# MotorCell.net
KiCad netlist of a schematic drawn in Altium Designer
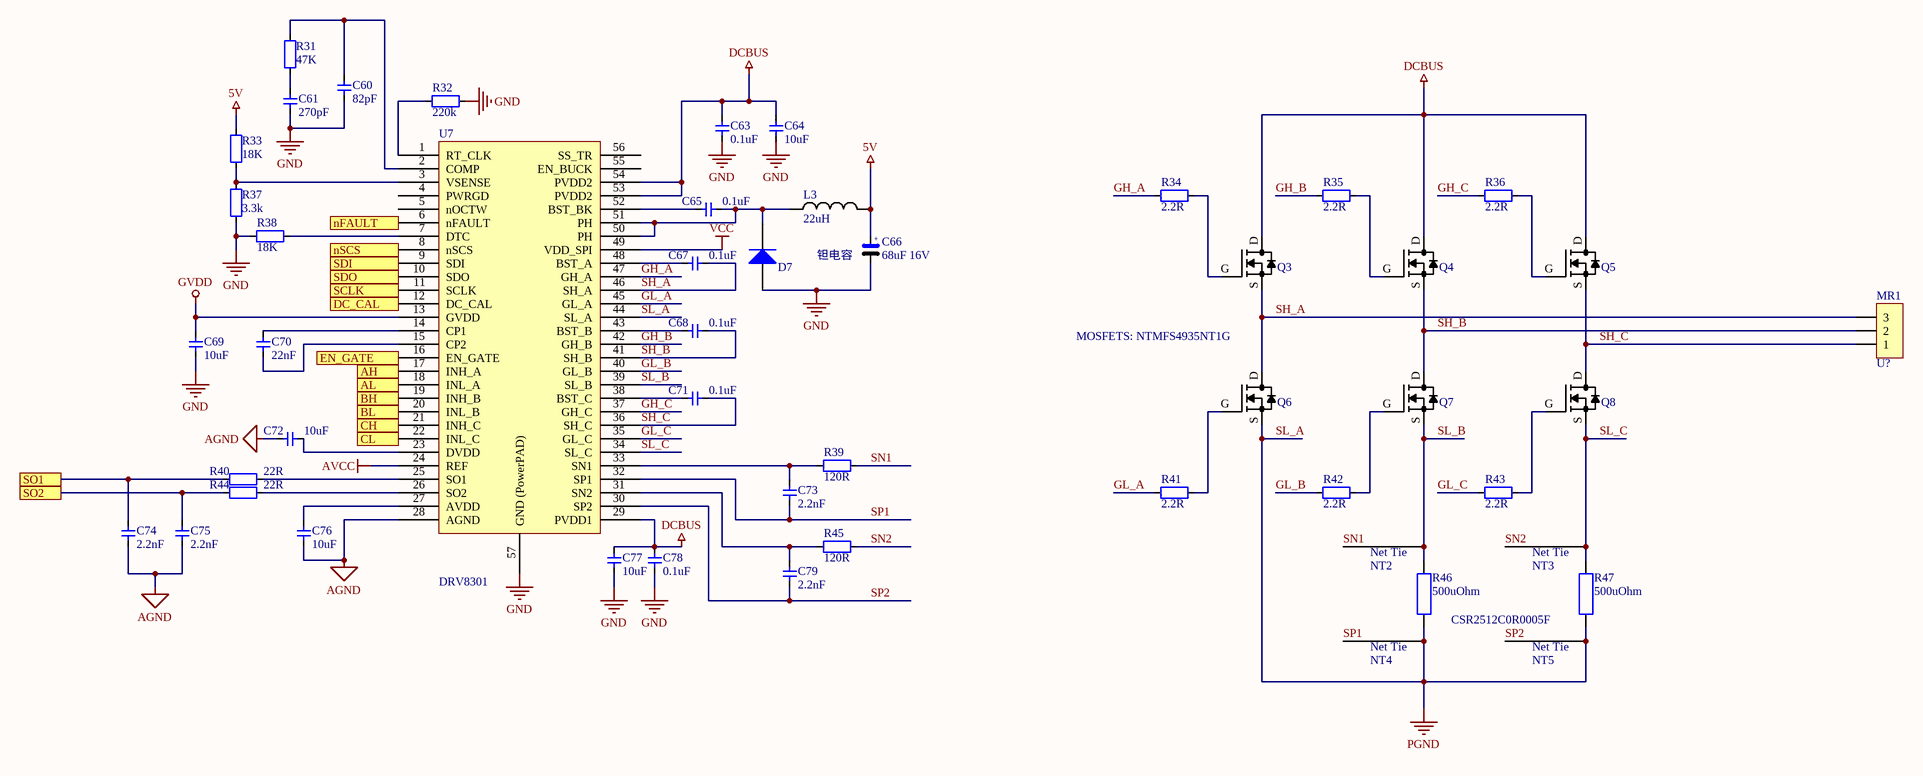
[diagram p0: MotorCell.SchDoc]

(export (version "E")
  (design (tool "Eeschema 10.0.6"))
  (components
    (comp (ref "C60")
      (value "82pF")
      (footprint "CAP_0402")
      (description "Capacitor")
      (libsource (lib "Ctrl_FOC") (part "电容-0402"))
    )
    (comp (ref "C61")
      (value "270pF")
      (footprint "CAP_0402")
      (description "Capacitor")
      (libsource (lib "Ctrl_FOC") (part "电容-0402"))
    )
    (comp (ref "C63")
      (value "0.1uF")
      (footprint "CAP_0603")
      (description "Capacitor")
      (libsource (lib "Ctrl_FOC") (part "电容-0603"))
    )
    (comp (ref "C64")
      (value "10uF")
      (footprint "CAP_0603")
      (description "Capacitor")
      (libsource (lib "Ctrl_FOC") (part "电容-0603"))
    )
    (comp (ref "C65")
      (value "0.1uF")
      (footprint "CAP_0402")
      (description "Capacitor")
      (libsource (lib "Ctrl_FOC") (part "电容-0402"))
    )
    (comp (ref "C66")
      (value "68uF 16V")
      (footprint "CAPCP6032X28N")
      (libsource (lib "Ctrl_FOC") (part "钽电容"))
    )
    (comp (ref "C67")
      (value "0.1uF")
      (footprint "CAP_0603")
      (description "Capacitor")
      (libsource (lib "Ctrl_FOC") (part "电容-0603"))
    )
    (comp (ref "C68")
      (value "0.1uF")
      (footprint "CAP_0603")
      (description "Capacitor")
      (libsource (lib "Ctrl_FOC") (part "电容-0603"))
    )
    (comp (ref "C69")
      (value "10uF")
      (footprint "CAP_0402")
      (description "Capacitor")
      (libsource (lib "Ctrl_FOC") (part "电容-0402"))
    )
    (comp (ref "C70")
      (value "22nF")
      (footprint "CAP_0402")
      (description "Capacitor")
      (libsource (lib "Ctrl_FOC") (part "电容-0402"))
    )
    (comp (ref "C71")
      (value "0.1uF")
      (footprint "CAP_0603")
      (description "Capacitor")
      (libsource (lib "Ctrl_FOC") (part "电容-0603"))
    )
    (comp (ref "C72")
      (value "10uF")
      (footprint "CAP_0402")
      (description "Capacitor")
      (libsource (lib "Ctrl_FOC") (part "电容-0402"))
    )
    (comp (ref "C73")
      (value "2.2nF")
      (footprint "CAP_0402")
      (description "Capacitor")
      (libsource (lib "Ctrl_FOC") (part "电容-0402"))
    )
    (comp (ref "C74")
      (value "2.2nF")
      (footprint "CAP_0402")
      (description "Capacitor")
      (libsource (lib "Ctrl_FOC") (part "电容-0402"))
    )
    (comp (ref "C75")
      (value "2.2nF")
      (footprint "CAP_0402")
      (description "Capacitor")
      (libsource (lib "Ctrl_FOC") (part "电容-0402"))
    )
    (comp (ref "C76")
      (value "10uF")
      (footprint "CAP_0402")
      (description "Capacitor")
      (libsource (lib "Ctrl_FOC") (part "电容-0402"))
    )
    (comp (ref "C77")
      (value "10uF")
      (footprint "CAP_0603")
      (description "Capacitor")
      (libsource (lib "Ctrl_FOC") (part "电容-0603"))
    )
    (comp (ref "C78")
      (value "0.1uF")
      (footprint "CAP_0603")
      (description "Capacitor")
      (libsource (lib "Ctrl_FOC") (part "电容-0603"))
    )
    (comp (ref "C79")
      (value "2.2nF")
      (footprint "CAP_0402")
      (description "Capacitor")
      (libsource (lib "Ctrl_FOC") (part "电容-0402"))
    )
    (comp (ref "D7")
      (value "MBR140SFT1G")
      (footprint "DIOM2717X10N")
      (description "Rectifier Diode, Single, 40 V, 1 A, SOD-123FL, 2, 550 mV")
      (libsource (lib "Ctrl_FOC") (part "MBR140SFT1G"))
    )
    (comp (ref "L3")
      (value "22uH")
      (footprint "INDC6060X28N")
      (description "INDUCTOR 22UH 1.4A 175.5 MOHM")
      (libsource (lib "Ctrl_FOC") (part "NR6028T220M"))
    )
    (comp (ref "MR1")
      (value "U?")
      (footprint "MR30PW-M")
      (description "MR30PW-M 三芯")
      (libsource (lib "VectorController") (part "MR30PW-M"))
    )
    (comp (ref "NT2")
      (value "0.25mm")
      (footprint "NetTie_0.25mm")
      (libsource (lib "Ctrl_FOC") (part "NetTie_0.25mm"))
    )
    (comp (ref "NT3")
      (value "0.25mm")
      (footprint "NetTie_0.25mm")
      (libsource (lib "Ctrl_FOC") (part "NetTie_0.25mm"))
    )
    (comp (ref "NT4")
      (value "0.25mm")
      (footprint "NetTie_0.25mm")
      (libsource (lib "Ctrl_FOC") (part "NetTie_0.25mm"))
    )
    (comp (ref "NT5")
      (value "0.25mm")
      (footprint "NetTie_0.25mm")
      (libsource (lib "Ctrl_FOC") (part "NetTie_0.25mm"))
    )
    (comp (ref "Q3")
      (value "NTMFS4935NT1G")
      (footprint "SO8FL")
      (description "MOSFET N-CH 30V 13A SO8FL")
      (fields (field (name "MANUFACTURER") "ON Semiconductor"))
      (libsource (lib "Ctrl_FOC") (part "NTMFS4935NT1G"))
    )
    (comp (ref "Q4")
      (value "NTMFS4935NT1G")
      (footprint "SO8FL")
      (description "MOSFET N-CH 30V 13A SO8FL")
      (fields (field (name "MANUFACTURER") "ON Semiconductor"))
      (libsource (lib "Ctrl_FOC") (part "NTMFS4935NT1G"))
    )
    (comp (ref "Q5")
      (value "NTMFS4935NT1G")
      (footprint "SO8FL")
      (description "MOSFET N-CH 30V 13A SO8FL")
      (fields (field (name "MANUFACTURER") "ON Semiconductor"))
      (libsource (lib "Ctrl_FOC") (part "NTMFS4935NT1G"))
    )
    (comp (ref "Q6")
      (value "NTMFS4935NT1G")
      (footprint "SO8FL")
      (description "MOSFET N-CH 30V 13A SO8FL")
      (fields (field (name "MANUFACTURER") "ON Semiconductor"))
      (libsource (lib "Ctrl_FOC") (part "NTMFS4935NT1G"))
    )
    (comp (ref "Q7")
      (value "NTMFS4935NT1G")
      (footprint "SO8FL")
      (description "MOSFET N-CH 30V 13A SO8FL")
      (fields (field (name "MANUFACTURER") "ON Semiconductor"))
      (libsource (lib "Ctrl_FOC") (part "NTMFS4935NT1G"))
    )
    (comp (ref "Q8")
      (value "NTMFS4935NT1G")
      (footprint "SO8FL")
      (description "MOSFET N-CH 30V 13A SO8FL")
      (fields (field (name "MANUFACTURER") "ON Semiconductor"))
      (libsource (lib "Ctrl_FOC") (part "NTMFS4935NT1G"))
    )
    (comp (ref "R31")
      (value "47K")
      (footprint "RES_0402")
      (description "Resistor")
      (libsource (lib "") (part "电阻-0402_1"))
    )
    (comp (ref "R32")
      (value "220k")
      (footprint "RES_0402")
      (description "Resistor")
      (libsource (lib "") (part "电阻-0402_2"))
    )
    (comp (ref "R33")
      (value "18K")
      (footprint "RES_0402")
      (description "Resistor")
      (libsource (lib "") (part "电阻-0402_1"))
    )
    (comp (ref "R34")
      (value "2.2R")
      (footprint "RES_0402")
      (description "Resistor")
      (libsource (lib "Ctrl_FOC") (part "电阻-0402"))
    )
    (comp (ref "R35")
      (value "2.2R")
      (footprint "RES_0402")
      (description "Resistor")
      (libsource (lib "Ctrl_FOC") (part "电阻-0402"))
    )
    (comp (ref "R36")
      (value "2.2R")
      (footprint "RES_0402")
      (description "Resistor")
      (libsource (lib "Ctrl_FOC") (part "电阻-0402"))
    )
    (comp (ref "R37")
      (value "3.3k")
      (footprint "RES_0402")
      (description "Resistor")
      (libsource (lib "") (part "电阻-0402_1"))
    )
    (comp (ref "R38")
      (value "18K")
      (footprint "RES_0402")
      (description "Resistor")
      (libsource (lib "Ctrl_FOC") (part "电阻-0402"))
    )
    (comp (ref "R39")
      (value "120R")
      (footprint "RES_0402")
      (description "Resistor")
      (libsource (lib "Ctrl_FOC") (part "电阻-0402"))
    )
    (comp (ref "R40")
      (value "22R")
      (footprint "RES_0402")
      (description "Resistor")
      (libsource (lib "Ctrl_FOC") (part "电阻-0402"))
    )
    (comp (ref "R41")
      (value "2.2R")
      (footprint "RES_0402")
      (description "Resistor")
      (libsource (lib "Ctrl_FOC") (part "电阻-0402"))
    )
    (comp (ref "R42")
      (value "2.2R")
      (footprint "RES_0402")
      (description "Resistor")
      (libsource (lib "Ctrl_FOC") (part "电阻-0402"))
    )
    (comp (ref "R43")
      (value "2.2R")
      (footprint "RES_0402")
      (description "Resistor")
      (libsource (lib "Ctrl_FOC") (part "电阻-0402"))
    )
    (comp (ref "R44")
      (value "22R")
      (footprint "RES_0402")
      (description "Resistor")
      (libsource (lib "Ctrl_FOC") (part "电阻-0402"))
    )
    (comp (ref "R45")
      (value "120R")
      (footprint "RES_0402")
      (description "Resistor")
      (libsource (lib "Ctrl_FOC") (part "电阻-0402"))
    )
    (comp (ref "R46")
      (value "500uOhm")
      (footprint "RESC6432X09N")
      (description "RES SMD 0.0005 OHM 1% 3W 2512")
      (fields (field (name "MANUFACTURER") "Riedon") (field (name "TOLERANCE") "±1%"))
      (libsource (lib "Ctrl_FOC") (part "CSR2512C0R0005F"))
    )
    (comp (ref "R47")
      (value "500uOhm")
      (footprint "RESC6432X09N")
      (description "RES SMD 0.0005 OHM 1% 3W 2512")
      (fields (field (name "MANUFACTURER") "Riedon") (field (name "TOLERANCE") "±1%"))
      (libsource (lib "Ctrl_FOC") (part "CSR2512C0R0005F"))
    )
    (comp (ref "U7")
      (value "DRV8301")
      (footprint "TSSOP50P810X120_HS-57N")
      (description "MOTOR DRIVER, 3PH, 56HTSSOP")
      (libsource (lib "Ctrl_FOC") (part "DRV8301"))
    )
  )
  (nets
    (net (code "1") (name "/AH") (class "Default")
      (node (ref "U7") (pin "17") (pinfunction "INH_A_17") (pintype "passive"))
    )
    (net (code "2") (name "/AL") (class "Default")
      (node (ref "U7") (pin "18") (pinfunction "INL_A_18") (pintype "passive"))
    )
    (net (code "3") (name "/BH") (class "Default")
      (node (ref "U7") (pin "19") (pinfunction "INH_B_19") (pintype "passive"))
    )
    (net (code "4") (name "/BL") (class "Default")
      (node (ref "U7") (pin "20") (pinfunction "INL_B_20") (pintype "passive"))
    )
    (net (code "5") (name "/CH") (class "Default")
      (node (ref "U7") (pin "21") (pinfunction "INH_C_21") (pintype "passive"))
    )
    (net (code "6") (name "/CL") (class "Default")
      (node (ref "U7") (pin "22") (pinfunction "INL_C_22") (pintype "passive"))
    )
    (net (code "7") (name "/DC_CAL") (class "Default")
      (node (ref "U7") (pin "12") (pinfunction "DC_CAL_12") (pintype "passive"))
    )
    (net (code "8") (name "/EN_GATE") (class "Default")
      (node (ref "U7") (pin "16") (pinfunction "EN_GATE_16") (pintype "passive"))
    )
    (net (code "9") (name "/GH_A") (class "Default")
      (node (ref "R34") (pin "1") (pinfunction "1_1") (pintype "passive"))
      (node (ref "U7") (pin "47") (pinfunction "GH_A_47") (pintype "passive"))
    )
    (net (code "10") (name "/GH_B") (class "Default")
      (node (ref "R35") (pin "1") (pinfunction "1_1") (pintype "passive"))
      (node (ref "U7") (pin "42") (pinfunction "GH_B_42") (pintype "passive"))
    )
    (net (code "11") (name "/GH_C") (class "Default")
      (node (ref "R36") (pin "1") (pinfunction "1_1") (pintype "passive"))
      (node (ref "U7") (pin "37") (pinfunction "GH_C_37") (pintype "passive"))
    )
    (net (code "12") (name "/GL_A") (class "Default")
      (node (ref "R41") (pin "1") (pinfunction "1_1") (pintype "passive"))
      (node (ref "U7") (pin "45") (pinfunction "GL_A_45") (pintype "passive"))
    )
    (net (code "13") (name "/GL_B") (class "Default")
      (node (ref "R42") (pin "1") (pinfunction "1_1") (pintype "passive"))
      (node (ref "U7") (pin "40") (pinfunction "GL_B_40") (pintype "passive"))
    )
    (net (code "14") (name "/GL_C") (class "Default")
      (node (ref "R43") (pin "1") (pinfunction "1_1") (pintype "passive"))
      (node (ref "U7") (pin "35") (pinfunction "GL_C_35") (pintype "passive"))
    )
    (net (code "15") (name "/SCLK") (class "Default")
      (node (ref "U7") (pin "11") (pinfunction "SCLK_11") (pintype "passive"))
    )
    (net (code "16") (name "/SDI") (class "Default")
      (node (ref "U7") (pin "9") (pinfunction "SDI_9") (pintype "passive"))
    )
    (net (code "17") (name "/SDO") (class "Default")
      (node (ref "U7") (pin "10") (pinfunction "SDO_10") (pintype "passive"))
    )
    (net (code "18") (name "/SH_A") (class "Default")
      (node (ref "C67") (pin "2") (pinfunction "2_2") (pintype "passive"))
      (node (ref "MR1") (pin "3") (pinfunction "3_3") (pintype "passive"))
      (node (ref "Q3") (pin "S") (pinfunction "S_S") (pintype "passive"))
      (node (ref "Q6") (pin "D") (pinfunction "D_D") (pintype "passive"))
      (node (ref "U7") (pin "46") (pinfunction "SH_A_46") (pintype "passive"))
    )
    (net (code "19") (name "/SH_B") (class "Default")
      (node (ref "C68") (pin "2") (pinfunction "2_2") (pintype "passive"))
      (node (ref "MR1") (pin "2") (pinfunction "2_2") (pintype "passive"))
      (node (ref "Q4") (pin "S") (pinfunction "S_S") (pintype "passive"))
      (node (ref "Q7") (pin "D") (pinfunction "D_D") (pintype "passive"))
      (node (ref "U7") (pin "41") (pinfunction "SH_B_41") (pintype "passive"))
    )
    (net (code "20") (name "/SH_C") (class "Default")
      (node (ref "C71") (pin "2") (pinfunction "2_2") (pintype "passive"))
      (node (ref "MR1") (pin "1") (pinfunction "1_1") (pintype "passive"))
      (node (ref "Q5") (pin "S") (pinfunction "S_S") (pintype "passive"))
      (node (ref "Q8") (pin "D") (pinfunction "D_D") (pintype "passive"))
      (node (ref "U7") (pin "36") (pinfunction "SH_C_36") (pintype "passive"))
    )
    (net (code "21") (name "/SL_B") (class "Default")
      (node (ref "NT2") (pin "2") (pintype "passive"))
      (node (ref "Q7") (pin "S") (pinfunction "S_S") (pintype "passive"))
      (node (ref "R46") (pin "2") (pinfunction "0_2") (pintype "passive"))
      (node (ref "U7") (pin "39") (pinfunction "SL_B_39") (pintype "passive"))
    )
    (net (code "22") (name "/SL_C") (class "Default")
      (node (ref "NT3") (pin "2") (pintype "passive"))
      (node (ref "Q8") (pin "S") (pinfunction "S_S") (pintype "passive"))
      (node (ref "R47") (pin "2") (pinfunction "0_2") (pintype "passive"))
      (node (ref "U7") (pin "34") (pinfunction "SL_C_34") (pintype "passive"))
    )
    (net (code "23") (name "/SN1") (class "Default")
      (node (ref "NT2") (pin "1") (pintype "passive"))
      (node (ref "R39") (pin "2") (pinfunction "2_2") (pintype "passive"))
    )
    (net (code "24") (name "/SN2") (class "Default")
      (node (ref "NT3") (pin "1") (pintype "passive"))
      (node (ref "R45") (pin "2") (pinfunction "2_2") (pintype "passive"))
    )
    (net (code "25") (name "/SO1") (class "Default")
      (node (ref "C74") (pin "2") (pinfunction "2_2") (pintype "passive"))
      (node (ref "R40") (pin "1") (pinfunction "1_1") (pintype "passive"))
    )
    (net (code "26") (name "/SO2") (class "Default")
      (node (ref "C75") (pin "2") (pinfunction "2_2") (pintype "passive"))
      (node (ref "R44") (pin "1") (pinfunction "1_1") (pintype "passive"))
    )
    (net (code "27") (name "/SP1") (class "Default")
      (node (ref "C73") (pin "1") (pinfunction "1_1") (pintype "passive"))
      (node (ref "NT4") (pin "1") (pintype "passive"))
      (node (ref "U7") (pin "32") (pinfunction "SP1_32") (pintype "passive"))
    )
    (net (code "28") (name "/SP2") (class "Default")
      (node (ref "C79") (pin "1") (pinfunction "1_1") (pintype "passive"))
      (node (ref "NT5") (pin "1") (pintype "passive"))
      (node (ref "U7") (pin "30") (pinfunction "SP2_30") (pintype "passive"))
    )
    (net (code "29") (name "/nFAULT") (class "Default")
      (node (ref "U7") (pin "6") (pinfunction "nFAULT_6") (pintype "passive"))
    )
    (net (code "30") (name "/nSCS") (class "Default")
      (node (ref "U7") (pin "8") (pinfunction "nSCS_8") (pintype "passive"))
    )
    (net (code "31") (name "5V") (class "Default")
      (node (ref "C66") (pin "1") (pinfunction "1_1") (pintype "passive"))
      (node (ref "L3") (pin "2") (pinfunction "2_2") (pintype "passive"))
      (node (ref "R33") (pin "2") (pinfunction "2_2") (pintype "passive"))
    )
    (net (code "32") (name "AGND") (class "Default")
      (node (ref "C72") (pin "2") (pinfunction "2_2") (pintype "passive"))
      (node (ref "C74") (pin "1") (pinfunction "1_1") (pintype "passive"))
      (node (ref "C75") (pin "1") (pinfunction "1_1") (pintype "passive"))
      (node (ref "C76") (pin "1") (pinfunction "1_1") (pintype "passive"))
      (node (ref "U7") (pin "28") (pinfunction "AGND_28") (pintype "passive"))
    )
    (net (code "33") (name "AVCC") (class "Default")
      (node (ref "U7") (pin "24") (pinfunction "REF_24") (pintype "passive"))
    )
    (net (code "34") (name "DCBUS") (class "Default")
      (node (ref "C63") (pin "2") (pinfunction "2_2") (pintype "passive"))
      (node (ref "C64") (pin "2") (pinfunction "2_2") (pintype "passive"))
      (node (ref "C77") (pin "2") (pinfunction "2_2") (pintype "passive"))
      (node (ref "C78") (pin "2") (pinfunction "2_2") (pintype "passive"))
      (node (ref "Q3") (pin "D") (pinfunction "D_D") (pintype "passive"))
      (node (ref "Q4") (pin "D") (pinfunction "D_D") (pintype "passive"))
      (node (ref "Q5") (pin "D") (pinfunction "D_D") (pintype "passive"))
      (node (ref "U7") (pin "29") (pinfunction "PVDD1_29") (pintype "passive"))
      (node (ref "U7") (pin "53") (pinfunction "PVDD2_53") (pintype "passive"))
      (node (ref "U7") (pin "54") (pinfunction "PVDD2_54") (pintype "passive"))
    )
    (net (code "35") (name "GND") (class "Default")
      (node (ref "C60") (pin "2") (pinfunction "2_2") (pintype "passive"))
      (node (ref "C61") (pin "2") (pinfunction "2_2") (pintype "passive"))
      (node (ref "C63") (pin "1") (pinfunction "1_1") (pintype "passive"))
      (node (ref "C64") (pin "1") (pinfunction "1_1") (pintype "passive"))
      (node (ref "C66") (pin "2") (pinfunction "2_2") (pintype "passive"))
      (node (ref "C69") (pin "1") (pinfunction "1_1") (pintype "passive"))
      (node (ref "C77") (pin "1") (pinfunction "1_1") (pintype "passive"))
      (node (ref "C78") (pin "1") (pinfunction "1_1") (pintype "passive"))
      (node (ref "D7") (pin "A") (pinfunction "A_A") (pintype "passive"))
      (node (ref "R32") (pin "1") (pinfunction "1_1") (pintype "passive"))
      (node (ref "R37") (pin "1") (pinfunction "1_1") (pintype "passive"))
      (node (ref "R38") (pin "1") (pinfunction "1_1") (pintype "passive"))
      (node (ref "U7") (pin "57") (pinfunction "GND_(PowerPAD)_57") (pintype "passive"))
    )
    (net (code "36") (name "GVDD") (class "Default")
      (node (ref "C69") (pin "2") (pinfunction "2_2") (pintype "passive"))
      (node (ref "U7") (pin "13") (pinfunction "GVDD_13") (pintype "passive"))
    )
    (net (code "37") (name "Net-(C61-Pad1)") (class "Default")
      (node (ref "C61") (pin "1") (pinfunction "1_1") (pintype "passive"))
      (node (ref "R31") (pin "1") (pinfunction "1_1") (pintype "passive"))
    )
    (net (code "38") (name "Net-(C65-Pad1)") (class "Default")
      (node (ref "C65") (pin "1") (pinfunction "1_1") (pintype "passive"))
      (node (ref "D7") (pin "K") (pinfunction "K_K") (pintype "passive"))
      (node (ref "L3") (pin "1") (pinfunction "1_1") (pintype "passive"))
      (node (ref "U7") (pin "50") (pinfunction "PH_50") (pintype "passive"))
      (node (ref "U7") (pin "51") (pinfunction "PH_51") (pintype "passive"))
    )
    (net (code "39") (name "Net-(Q3-PadG)") (class "Default")
      (node (ref "Q3") (pin "G") (pinfunction "G_G") (pintype "passive"))
      (node (ref "R34") (pin "2") (pinfunction "2_2") (pintype "passive"))
    )
    (net (code "40") (name "Net-(Q4-PadG)") (class "Default")
      (node (ref "Q4") (pin "G") (pinfunction "G_G") (pintype "passive"))
      (node (ref "R35") (pin "2") (pinfunction "2_2") (pintype "passive"))
    )
    (net (code "41") (name "Net-(Q5-PadG)") (class "Default")
      (node (ref "Q5") (pin "G") (pinfunction "G_G") (pintype "passive"))
      (node (ref "R36") (pin "2") (pinfunction "2_2") (pintype "passive"))
    )
    (net (code "42") (name "Net-(Q6-PadG)") (class "Default")
      (node (ref "Q6") (pin "G") (pinfunction "G_G") (pintype "passive"))
      (node (ref "R41") (pin "2") (pinfunction "2_2") (pintype "passive"))
    )
    (net (code "43") (name "Net-(Q7-PadG)") (class "Default")
      (node (ref "Q7") (pin "G") (pinfunction "G_G") (pintype "passive"))
      (node (ref "R42") (pin "2") (pinfunction "2_2") (pintype "passive"))
    )
    (net (code "44") (name "Net-(Q8-PadG)") (class "Default")
      (node (ref "Q8") (pin "G") (pinfunction "G_G") (pintype "passive"))
      (node (ref "R43") (pin "2") (pinfunction "2_2") (pintype "passive"))
    )
    (net (code "45") (name "Net-(U7-AVDD)") (class "Default")
      (node (ref "C76") (pin "2") (pinfunction "2_2") (pintype "passive"))
      (node (ref "U7") (pin "27") (pinfunction "AVDD_27") (pintype "passive"))
    )
    (net (code "46") (name "Net-(U7-BST_A)") (class "Default")
      (node (ref "C67") (pin "1") (pinfunction "1_1") (pintype "passive"))
      (node (ref "U7") (pin "48") (pinfunction "BST_A_48") (pintype "passive"))
    )
    (net (code "47") (name "Net-(U7-BST_B)") (class "Default")
      (node (ref "C68") (pin "1") (pinfunction "1_1") (pintype "passive"))
      (node (ref "U7") (pin "43") (pinfunction "BST_B_43") (pintype "passive"))
    )
    (net (code "48") (name "Net-(U7-BST_BK)") (class "Default")
      (node (ref "C65") (pin "2") (pinfunction "2_2") (pintype "passive"))
      (node (ref "U7") (pin "52") (pinfunction "BST_BK_52") (pintype "passive"))
    )
    (net (code "49") (name "Net-(U7-BST_C)") (class "Default")
      (node (ref "C71") (pin "1") (pinfunction "1_1") (pintype "passive"))
      (node (ref "U7") (pin "38") (pinfunction "BST_C_38") (pintype "passive"))
    )
    (net (code "50") (name "Net-(U7-COMP)") (class "Default")
      (node (ref "C60") (pin "1") (pinfunction "1_1") (pintype "passive"))
      (node (ref "R31") (pin "2") (pinfunction "2_2") (pintype "passive"))
      (node (ref "U7") (pin "2") (pinfunction "COMP_2") (pintype "passive"))
    )
    (net (code "51") (name "Net-(U7-CP1)") (class "Default")
      (node (ref "C70") (pin "1") (pinfunction "1_1") (pintype "passive"))
      (node (ref "U7") (pin "14") (pinfunction "CP1_14") (pintype "passive"))
    )
    (net (code "52") (name "Net-(U7-CP2)") (class "Default")
      (node (ref "C70") (pin "2") (pinfunction "2_2") (pintype "passive"))
      (node (ref "U7") (pin "15") (pinfunction "CP2_15") (pintype "passive"))
    )
    (net (code "53") (name "Net-(U7-DTC)") (class "Default")
      (node (ref "R38") (pin "2") (pinfunction "2_2") (pintype "passive"))
      (node (ref "U7") (pin "7") (pinfunction "DTC_7") (pintype "passive"))
    )
    (net (code "54") (name "Net-(U7-DVDD)") (class "Default")
      (node (ref "C72") (pin "1") (pinfunction "1_1") (pintype "passive"))
      (node (ref "U7") (pin "23") (pinfunction "DVDD_23") (pintype "passive"))
    )
    (net (code "55") (name "Net-(U7-RT_CLK)") (class "Default")
      (node (ref "R32") (pin "2") (pinfunction "2_2") (pintype "passive"))
      (node (ref "U7") (pin "1") (pinfunction "RT_CLK_1") (pintype "passive"))
    )
    (net (code "56") (name "Net-(U7-SN1)") (class "Default")
      (node (ref "C73") (pin "2") (pinfunction "2_2") (pintype "passive"))
      (node (ref "R39") (pin "1") (pinfunction "1_1") (pintype "passive"))
      (node (ref "U7") (pin "33") (pinfunction "SN1_33") (pintype "passive"))
    )
    (net (code "57") (name "Net-(U7-SN2)") (class "Default")
      (node (ref "C79") (pin "2") (pinfunction "2_2") (pintype "passive"))
      (node (ref "R45") (pin "1") (pinfunction "1_1") (pintype "passive"))
      (node (ref "U7") (pin "31") (pinfunction "SN2_31") (pintype "passive"))
    )
    (net (code "58") (name "Net-(U7-SO1)") (class "Default")
      (node (ref "R40") (pin "2") (pinfunction "2_2") (pintype "passive"))
      (node (ref "U7") (pin "25") (pinfunction "SO1_25") (pintype "passive"))
    )
    (net (code "59") (name "Net-(U7-SO2)") (class "Default")
      (node (ref "R44") (pin "2") (pinfunction "2_2") (pintype "passive"))
      (node (ref "U7") (pin "26") (pinfunction "SO2_26") (pintype "passive"))
    )
    (net (code "60") (name "Net-(U7-VSENSE)") (class "Default")
      (node (ref "R33") (pin "1") (pinfunction "1_1") (pintype "passive"))
      (node (ref "R37") (pin "2") (pinfunction "2_2") (pintype "passive"))
      (node (ref "U7") (pin "3") (pinfunction "VSENSE_3") (pintype "passive"))
    )
    (net (code "61") (name "PGND") (class "Default")
      (node (ref "NT4") (pin "2") (pintype "passive"))
      (node (ref "NT5") (pin "2") (pintype "passive"))
      (node (ref "Q6") (pin "S") (pinfunction "S_S") (pintype "passive"))
      (node (ref "R46") (pin "1") (pinfunction "0_1") (pintype "passive"))
      (node (ref "R47") (pin "1") (pinfunction "0_1") (pintype "passive"))
      (node (ref "U7") (pin "44") (pinfunction "SL_A_44") (pintype "passive"))
    )
    (net (code "62") (name "VCC") (class "Default")
      (node (ref "U7") (pin "49") (pinfunction "VDD_SPI_49") (pintype "passive"))
    )
    (net (code "63") (name "unconnected-(U7-EN_BUCK-Pad55)") (class "Default")
      (node (ref "U7") (pin "55") (pinfunction "EN_BUCK_55") (pintype "passive"))
    )
    (net (code "64") (name "unconnected-(U7-PWRGD-Pad4)") (class "Default")
      (node (ref "U7") (pin "4") (pinfunction "PWRGD_4") (pintype "passive"))
    )
    (net (code "65") (name "unconnected-(U7-SS_TR-Pad56)") (class "Default")
      (node (ref "U7") (pin "56") (pinfunction "SS_TR_56") (pintype "passive"))
    )
    (net (code "66") (name "unconnected-(U7-nOCTW-Pad5)") (class "Default")
      (node (ref "U7") (pin "5") (pinfunction "nOCTW_5") (pintype "passive"))
    )
  )
)
